# tb6612fng.net
KiCad netlist of a schematic drawn in Altium Designer
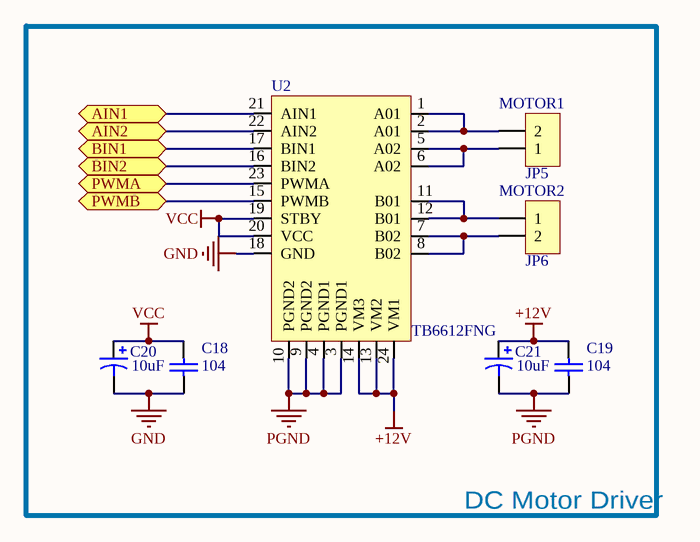
[diagram p0: tb6612fng.SchDoc]

(export (version "E")
  (design (tool "Eeschema 10.0.6"))
  (components
    (comp (ref "C18")
      (value "104")
      (footprint "C 0603_L")
      (description "Capacitor")
      (fields (field (name "PUBLISHER") "Altium Limited"))
      (libsource (lib "Miscellaneous Devices") (part "Cap"))
    )
    (comp (ref "C19")
      (value "104")
      (footprint "C 0603_L")
      (description "Capacitor")
      (fields (field (name "PUBLISHER") "Altium Limited"))
      (libsource (lib "Miscellaneous Devices") (part "Cap"))
    )
    (comp (ref "C20")
      (value "10uF")
      (footprint "CD A(3216)")
      (description "Polarized Capacitor (Radial)")
      (fields (field (name "PUBLISHER") "Altium Limited"))
      (libsource (lib "Miscellaneous Devices") (part "Cap Pol1"))
    )
    (comp (ref "C21")
      (value "10uF")
      (footprint "CD A(3216)")
      (description "Polarized Capacitor (Radial)")
      (fields (field (name "PUBLISHER") "Altium Limited"))
      (libsource (lib "Miscellaneous Devices") (part "Cap Pol1"))
    )
    (comp (ref "JP5")
      (value "MOTOR1")
      (footprint "XH2.54-LI-2P")
      (description "2P接插件")
      (fields (field (name "版权归属") "源创客"))
      (libsource (lib "") (part "Header 2_1"))
    )
    (comp (ref "JP6")
      (value "MOTOR2")
      (footprint "XH2.54-LI-2P")
      (description "2P接插件")
      (fields (field (name "版权归属") "源创客"))
      (libsource (lib "4.5   - 接插件-脚距2.54") (part "Header 2"))
    )
    (comp (ref "U2")
      (value "TB6612FNG")
      (footprint "SSOP24_N")
      (description "DC_MOTOR_DRIVER")
      (libsource (lib "主控板载芯片") (part "TB6612FNG"))
    )
  )
  (nets
    (net (code "1") (name "+12V") (class "Default")
      (node (ref "C19") (pin "2") (pinfunction "2_2") (pintype "passive"))
      (node (ref "C21") (pin "1") (pinfunction "1_1") (pintype "passive"))
      (node (ref "U2") (pin "13") (pinfunction "VM2_13") (pintype "passive"))
      (node (ref "U2") (pin "14") (pinfunction "VM3_14") (pintype "passive"))
      (node (ref "U2") (pin "24") (pinfunction "VM1_24") (pintype "passive"))
    )
    (net (code "2") (name "/AIN1") (class "Default")
      (node (ref "U2") (pin "21") (pinfunction "AIN1_21") (pintype "passive"))
    )
    (net (code "3") (name "/AIN2") (class "Default")
      (node (ref "U2") (pin "22") (pinfunction "AIN2_22") (pintype "passive"))
    )
    (net (code "4") (name "/BIN1") (class "Default")
      (node (ref "U2") (pin "17") (pinfunction "BIN1_17") (pintype "passive"))
    )
    (net (code "5") (name "/BIN2") (class "Default")
      (node (ref "U2") (pin "16") (pinfunction "BIN2_16") (pintype "passive"))
    )
    (net (code "6") (name "/PWMA") (class "Default")
      (node (ref "U2") (pin "23") (pinfunction "PWMA_23") (pintype "passive"))
    )
    (net (code "7") (name "/PWMB") (class "Default")
      (node (ref "U2") (pin "15") (pinfunction "PWMB_15") (pintype "passive"))
    )
    (net (code "8") (name "GND") (class "Default")
      (node (ref "C18") (pin "1") (pinfunction "1_1") (pintype "passive"))
      (node (ref "C20") (pin "2") (pinfunction "2_2") (pintype "passive"))
      (node (ref "U2") (pin "18") (pinfunction "GND_18") (pintype "passive"))
    )
    (net (code "9") (name "Net-(JP5-Pad1)") (class "Default")
      (node (ref "JP5") (pin "1") (pinfunction "1_1") (pintype "passive"))
      (node (ref "U2") (pin "5") (pinfunction "A02_5") (pintype "passive"))
      (node (ref "U2") (pin "6") (pinfunction "A02_6") (pintype "passive"))
    )
    (net (code "10") (name "Net-(JP5-Pad2)") (class "Default")
      (node (ref "JP5") (pin "2") (pinfunction "2_2") (pintype "passive"))
      (node (ref "U2") (pin "1") (pinfunction "A01_1") (pintype "passive"))
      (node (ref "U2") (pin "2") (pinfunction "A01_2") (pintype "passive"))
    )
    (net (code "11") (name "Net-(JP6-Pad1)") (class "Default")
      (node (ref "JP6") (pin "1") (pinfunction "1_1") (pintype "passive"))
      (node (ref "U2") (pin "11") (pinfunction "B01_11") (pintype "passive"))
      (node (ref "U2") (pin "12") (pinfunction "B01_12") (pintype "passive"))
    )
    (net (code "12") (name "Net-(JP6-Pad2)") (class "Default")
      (node (ref "JP6") (pin "2") (pinfunction "2_2") (pintype "passive"))
      (node (ref "U2") (pin "7") (pinfunction "B02_7") (pintype "passive"))
      (node (ref "U2") (pin "8") (pinfunction "B02_8") (pintype "passive"))
    )
    (net (code "13") (name "PGND") (class "Default")
      (node (ref "C19") (pin "1") (pinfunction "1_1") (pintype "passive"))
      (node (ref "C21") (pin "2") (pinfunction "2_2") (pintype "passive"))
      (node (ref "U2") (pin "10") (pinfunction "PGND2_10") (pintype "passive"))
      (node (ref "U2") (pin "3") (pinfunction "PGND1_3") (pintype "passive"))
      (node (ref "U2") (pin "4") (pinfunction "PGND1_4") (pintype "passive"))
      (node (ref "U2") (pin "9") (pinfunction "PGND2_9") (pintype "passive"))
    )
    (net (code "14") (name "VCC") (class "Default")
      (node (ref "C18") (pin "2") (pinfunction "2_2") (pintype "passive"))
      (node (ref "C20") (pin "1") (pinfunction "1_1") (pintype "passive"))
      (node (ref "U2") (pin "19") (pinfunction "STBY_19") (pintype "passive"))
      (node (ref "U2") (pin "20") (pinfunction "VCC_20") (pintype "passive"))
    )
  )
)
